# picaxe-08-trainer.net
KiCad netlist of a schematic drawn in EAGLE
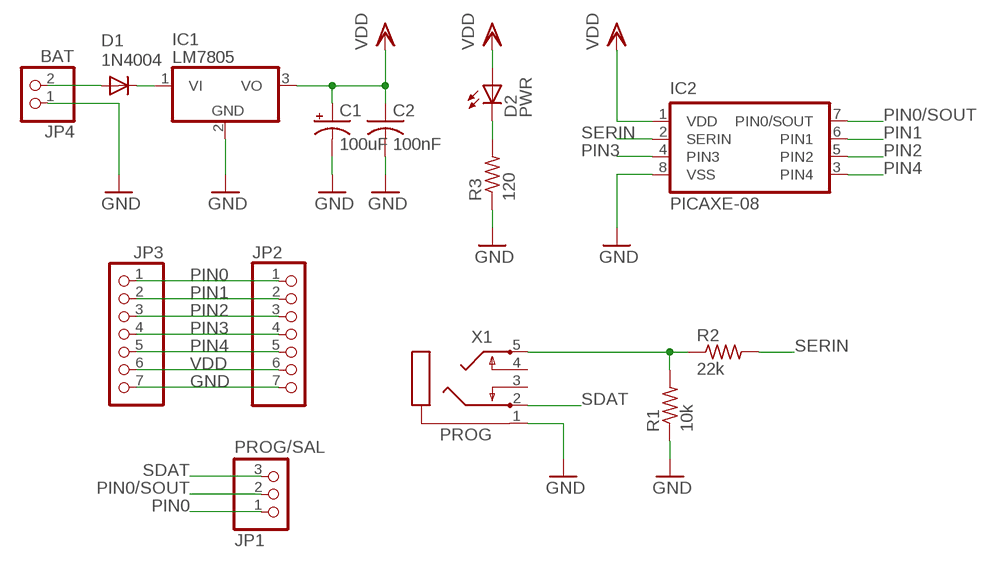
[diagram p0: schematic, sheet 1]

(export (version "E")
  (design (tool "Eeschema 10.0.6"))
  (components
    (comp (ref "C1")
      (value "100uF")
      (footprint "eagle-import:E5-6")
      (libsource (lib "eagle-import") (part "CPOL-USE5-6"))
    )
    (comp (ref "C2")
      (value "100nF")
      (footprint "eagle-import:C025-025X050")
      (libsource (lib "eagle-import") (part "C-US025-025X050"))
    )
    (comp (ref "D1")
      (value "1N4004")
      (footprint "eagle-import:DO41-10")
      (libsource (lib "eagle-import") (part "1N4004"))
    )
    (comp (ref "D2")
      (value "PWR")
      (footprint "eagle-import:LED3MM")
      (libsource (lib "eagle-import") (part "LED3MM"))
    )
    (comp (ref "IC1")
      (value "LM7805")
      (footprint "eagle-import:TO220V")
      (libsource (lib "eagle-import") (part "78TV05"))
    )
    (comp (ref "IC2")
      (value "PICAXE-08")
      (footprint "eagle-import:DIL8")
      (libsource (lib "eagle-import") (part "PICAXE-08"))
    )
    (comp (ref "JP1")
      (value "PROG/SAL")
      (footprint "eagle-import:1X03")
      (libsource (lib "eagle-import") (part "PINHD-1X3"))
    )
    (comp (ref "JP2")
      (value "PINHD-1X7")
      (footprint "eagle-import:1X07")
      (libsource (lib "eagle-import") (part "PINHD-1X7"))
    )
    (comp (ref "JP3")
      (value "PINHD-1X7")
      (footprint "eagle-import:1X07")
      (libsource (lib "eagle-import") (part "PINHD-1X7"))
    )
    (comp (ref "JP4")
      (value "BAT")
      (footprint "eagle-import:1X02")
      (libsource (lib "eagle-import") (part "PINHD-1X2"))
    )
    (comp (ref "R1")
      (value "10k")
      (footprint "eagle-import:0204_7")
      (libsource (lib "eagle-import") (part "R-US_0204/7"))
    )
    (comp (ref "R2")
      (value "22k")
      (footprint "eagle-import:0204_7")
      (libsource (lib "eagle-import") (part "R-US_0204/7"))
    )
    (comp (ref "R3")
      (value "120")
      (footprint "eagle-import:0204_7")
      (libsource (lib "eagle-import") (part "R-US_0204/7"))
    )
    (comp (ref "X1")
      (value "PROG")
      (footprint "eagle-import:STX3100")
      (libsource (lib "eagle-import") (part "STEREOJACK"))
    )
  )
  (nets
    (net (code "1") (name "/PIN0") (class "Default")
      (node (ref "JP1") (pin "1") (pinfunction "1_1") (pintype "passive"))
      (node (ref "JP2") (pin "1") (pinfunction "1_1") (pintype "passive"))
      (node (ref "JP3") (pin "1") (pinfunction "1_1") (pintype "passive"))
    )
    (net (code "2") (name "/PIN0{slash}SOUT") (class "Default")
      (node (ref "IC2") (pin "7") (pinfunction "PIN0/SOUT_7") (pintype "output"))
      (node (ref "JP1") (pin "2") (pinfunction "2_2") (pintype "passive"))
    )
    (net (code "3") (name "/PIN1") (class "Default")
      (node (ref "IC2") (pin "6") (pinfunction "PIN1_6") (pintype "bidirectional"))
      (node (ref "JP2") (pin "2") (pinfunction "2_2") (pintype "passive"))
      (node (ref "JP3") (pin "2") (pinfunction "2_2") (pintype "passive"))
    )
    (net (code "4") (name "/PIN2") (class "Default")
      (node (ref "IC2") (pin "5") (pinfunction "PIN2_5") (pintype "bidirectional"))
      (node (ref "JP2") (pin "3") (pinfunction "3_3") (pintype "passive"))
      (node (ref "JP3") (pin "3") (pinfunction "3_3") (pintype "passive"))
    )
    (net (code "5") (name "/PIN3") (class "Default")
      (node (ref "IC2") (pin "4") (pinfunction "PIN3_4") (pintype "input"))
      (node (ref "JP2") (pin "4") (pinfunction "4_4") (pintype "passive"))
      (node (ref "JP3") (pin "4") (pinfunction "4_4") (pintype "passive"))
    )
    (net (code "6") (name "/PIN4") (class "Default")
      (node (ref "IC2") (pin "3") (pinfunction "PIN4_3") (pintype "bidirectional"))
      (node (ref "JP2") (pin "5") (pinfunction "5_5") (pintype "passive"))
      (node (ref "JP3") (pin "5") (pinfunction "5_5") (pintype "passive"))
    )
    (net (code "7") (name "/SDAT") (class "Default")
      (node (ref "JP1") (pin "3") (pinfunction "3_3") (pintype "passive"))
      (node (ref "X1") (pin "2") (pinfunction "2_2") (pintype "passive"))
    )
    (net (code "8") (name "/SERIN") (class "Default")
      (node (ref "IC2") (pin "2") (pinfunction "SERIN_2") (pintype "bidirectional"))
      (node (ref "R2") (pin "2") (pinfunction "2_2") (pintype "passive"))
    )
    (net (code "9") (name "GND") (class "Default")
      (node (ref "C1") (pin "-") (pinfunction "-_-") (pintype "passive"))
      (node (ref "C2") (pin "2") (pinfunction "2_2") (pintype "passive"))
      (node (ref "IC1") (pin "2") (pinfunction "GND_2") (pintype "passive"))
      (node (ref "IC2") (pin "8") (pinfunction "VSS_8") (pintype "power_in"))
      (node (ref "JP2") (pin "7") (pinfunction "7_7") (pintype "passive"))
      (node (ref "JP3") (pin "7") (pinfunction "7_7") (pintype "passive"))
      (node (ref "JP4") (pin "1") (pinfunction "1_1") (pintype "passive"))
      (node (ref "R1") (pin "1") (pinfunction "1_1") (pintype "passive"))
      (node (ref "R3") (pin "1") (pinfunction "1_1") (pintype "passive"))
      (node (ref "X1") (pin "1") (pinfunction "1_1") (pintype "passive"))
    )
    (net (code "10") (name "Net-(D1-PadA)") (class "Default")
      (node (ref "D1") (pin "A") (pinfunction "A_A") (pintype "passive"))
      (node (ref "JP4") (pin "2") (pinfunction "2_2") (pintype "passive"))
    )
    (net (code "11") (name "Net-(D2-C)") (class "Default")
      (node (ref "D2") (pin "K") (pinfunction "C_K") (pintype "passive"))
      (node (ref "R3") (pin "2") (pinfunction "2_2") (pintype "passive"))
    )
    (net (code "12") (name "Net-(IC1-VI)") (class "Default")
      (node (ref "D1") (pin "C") (pinfunction "C_C") (pintype "passive"))
      (node (ref "IC1") (pin "1") (pinfunction "VI_1") (pintype "input"))
    )
    (net (code "13") (name "Net-(R1-Pad2)") (class "Default")
      (node (ref "R1") (pin "2") (pinfunction "2_2") (pintype "passive"))
      (node (ref "R2") (pin "1") (pinfunction "1_1") (pintype "passive"))
      (node (ref "X1") (pin "5") (pinfunction "5_5") (pintype "passive"))
    )
    (net (code "14") (name "VDD") (class "Default")
      (node (ref "C1") (pin "+") (pinfunction "+_+") (pintype "passive"))
      (node (ref "C2") (pin "1") (pinfunction "1_1") (pintype "passive"))
      (node (ref "D2") (pin "A") (pinfunction "A_A") (pintype "passive"))
      (node (ref "IC1") (pin "3") (pinfunction "VO_3") (pintype "passive"))
      (node (ref "IC2") (pin "1") (pinfunction "VDD_1") (pintype "power_in"))
      (node (ref "JP2") (pin "6") (pinfunction "6_6") (pintype "passive"))
      (node (ref "JP3") (pin "6") (pinfunction "6_6") (pintype "passive"))
    )
    (net (code "15") (name "unconnected-(X1-Pad3)") (class "Default")
      (node (ref "X1") (pin "3") (pinfunction "3_3") (pintype "passive"))
    )
    (net (code "16") (name "unconnected-(X1-Pad4)") (class "Default")
      (node (ref "X1") (pin "4") (pinfunction "4_4") (pintype "passive"))
    )
  )
)
